# RF.net
KiCad netlist of a schematic drawn in Altium Designer
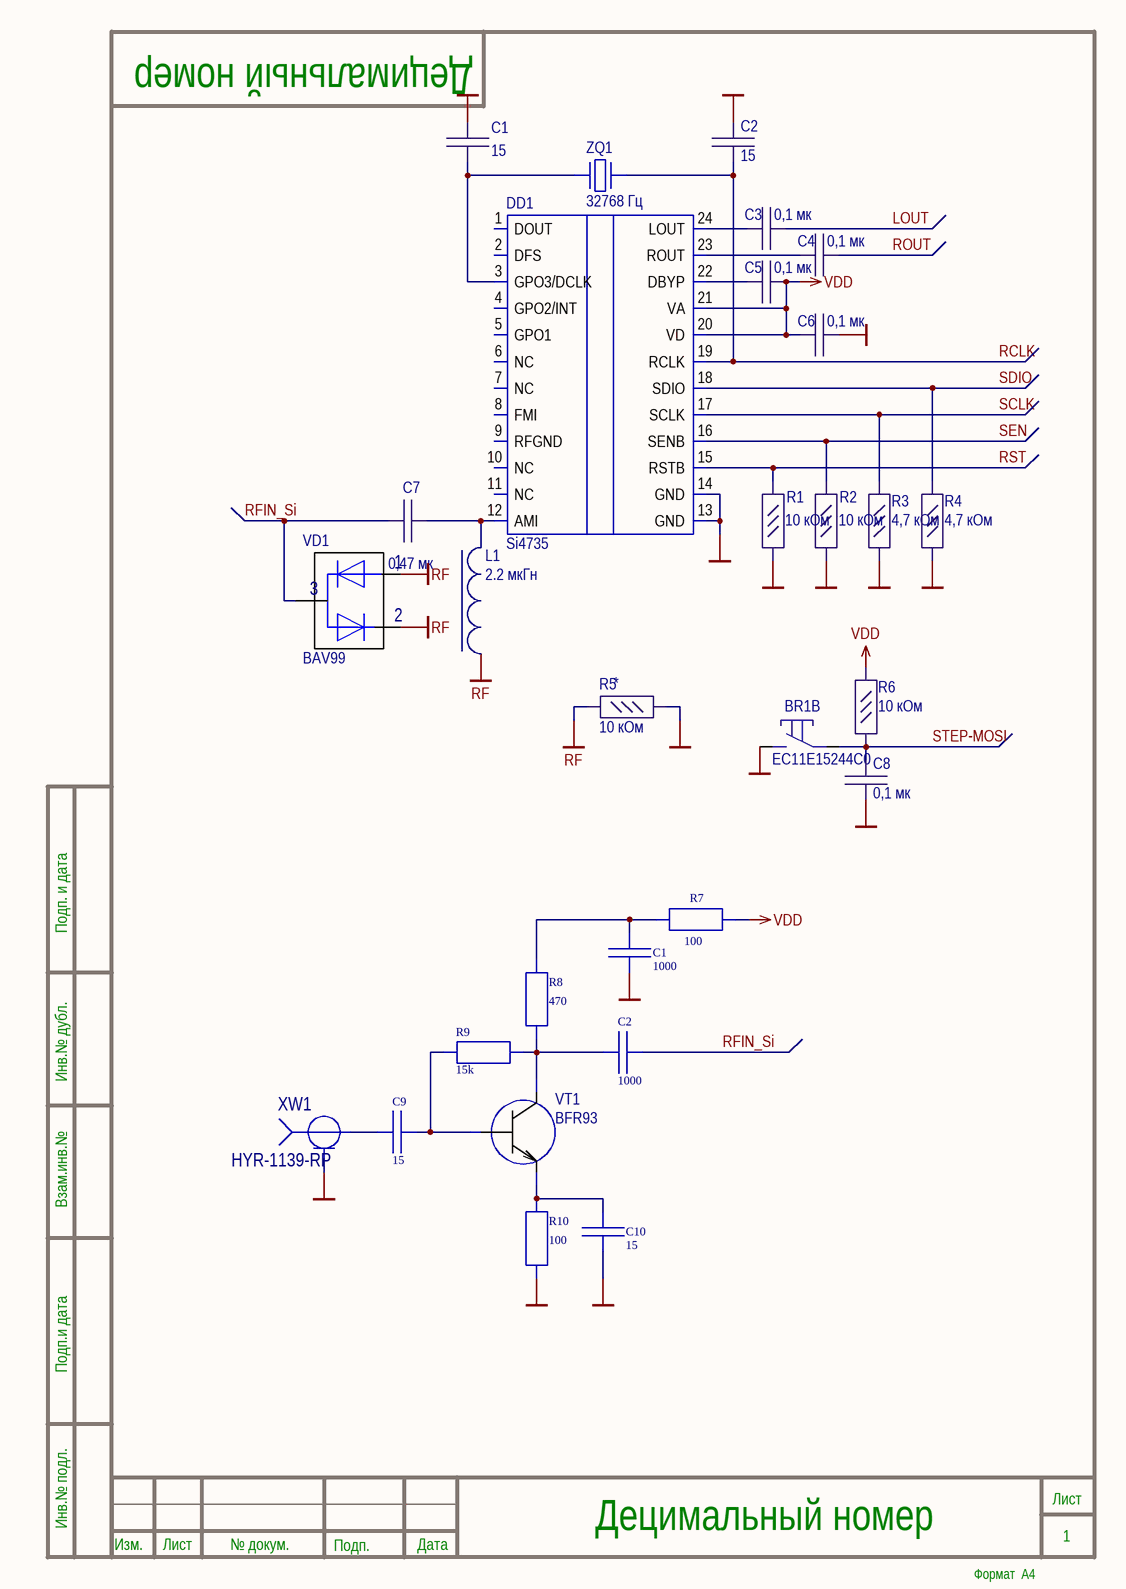
[diagram p0: RF.SchDoc]

(export (version "E")
  (design (tool "Eeschema 10.0.6"))
  (components
    (comp (ref "BR1")
      (value "EC11E15244C0")
      (footprint "EC11")
      (libsource (lib "9.Commutation") (part "EC11E15244C0"))
    )
    (comp (ref "C1")
      (value "15")
      (footprint "C_0603")
      (description "CAP CER 15PF 50V C0G/NP0 0603")
      (fields
        (field (name "PART NUMBER") "GRM1885C1H150FA01D")
        (field (name "MANUFACTURER") "Murata Electronics")
      )
      (libsource (lib "Database_Lib") (part "Capasitor"))
    )
    (comp (ref "C2")
      (value "15")
      (footprint "C_0603")
      (description "CAP CER 15PF 50V C0G/NP0 0603")
      (fields
        (field (name "PART NUMBER") "GRM1885C1H150FA01D")
        (field (name "MANUFACTURER") "Murata Electronics")
      )
      (libsource (lib "Database_Lib") (part "Capasitor"))
    )
    (comp (ref "C3")
      (value "0,1 мк")
      (footprint "C_0603")
      (description "CAP CER 0.1UF 100V X7R 0603")
      (fields
        (field (name "PART NUMBER") "GRM188R72A104MA35D")
        (field (name "MANUFACTURER") "Murata Electronics")
      )
      (libsource (lib "Database_Lib") (part "Capasitor"))
    )
    (comp (ref "C4")
      (value "0,1 мк")
      (footprint "C_0603")
      (description "CAP CER 0.1UF 100V X7R 0603")
      (fields
        (field (name "PART NUMBER") "GRM188R72A104MA35D")
        (field (name "MANUFACTURER") "Murata Electronics")
      )
      (libsource (lib "Database_Lib") (part "Capasitor"))
    )
    (comp (ref "C5")
      (value "0,1 мк")
      (footprint "C_0603")
      (description "CAP CER 0.1UF 100V X7R 0603")
      (fields
        (field (name "PART NUMBER") "GRM188R72A104MA35D")
        (field (name "MANUFACTURER") "Murata Electronics")
      )
      (libsource (lib "Database_Lib") (part "Capasitor"))
    )
    (comp (ref "C6")
      (value "0,1 мк")
      (footprint "C_0603")
      (description "CAP CER 0.1UF 100V X7R 0603")
      (fields
        (field (name "PART NUMBER") "GRM188R72A104MA35D")
        (field (name "MANUFACTURER") "Murata Electronics")
      )
      (libsource (lib "Database_Lib") (part "Capasitor"))
    )
    (comp (ref "C7")
      (value "0,47 мк")
      (footprint "C_0603")
      (description "CAP CER 0.47UF 25V X7R 0603")
      (fields
        (field (name "PART NUMBER") "GRM188R71E474KA12D")
        (field (name "MANUFACTURER") "Murata Electronics")
      )
      (libsource (lib "Database_Lib") (part "Capasitor"))
    )
    (comp (ref "C8")
      (value "0,1 мк")
      (footprint "C_0603")
      (description "CAP CER 0.1UF 100V X7R 0603")
      (fields
        (field (name "PART NUMBER") "GRM188R72A104MA35D")
        (field (name "MANUFACTURER") "Murata Electronics")
      )
      (libsource (lib "Database_Lib") (part "Capasitor"))
    )
    (comp (ref "C9")
      (value "15")
      (footprint "C_0603")
      (description "Cap. 15 pF, 0603")
      (libsource (lib "Schlib1") (part "06035C100KAT2A"))
    )
    (comp (ref "C10")
      (value "15")
      (footprint "C_0603")
      (description "Cap. 15 pF, 0603")
      (libsource (lib "Schlib1") (part "06035C100KAT2A"))
    )
    (comp (ref "DD1")
      (value "Si4735")
      (footprint "SSOP-24")
      (description "BROADCAST AM/FM/SW/LW RADIO RECEIVER")
      (libsource (lib "2. Chips") (part "Si4735"))
    )
    (comp (ref "L1")
      (value "2.2 мкГн")
      (footprint "LQW18A")
      (description "0.22 мкГн, 0603, 2%")
      (libsource (lib "11. Inductors") (part "LQW18ANR22G"))
    )
    (comp (ref "R1")
      (value "10 кОм")
      (footprint "R_0603")
      (description "RES SMD 10K OHM 1% 1/10W 0603")
      (fields (field (name "PART NUMBER") "CR0603-FX-1002ELF") (field (name "MANUFACTURER") "Bourns Inc."))
      (libsource (lib "Database_Lib") (part "Resistor"))
    )
    (comp (ref "R2")
      (value "10 кОм")
      (footprint "R_0603")
      (description "RES SMD 10K OHM 1% 1/10W 0603")
      (fields (field (name "PART NUMBER") "CR0603-FX-1002ELF") (field (name "MANUFACTURER") "Bourns Inc."))
      (libsource (lib "Database_Lib") (part "Resistor"))
    )
    (comp (ref "R3")
      (value "4,7 кОм")
      (footprint "R_0603")
      (description "RES SMD 4.7K OHM 1% 1/10W 0603")
      (fields (field (name "PART NUMBER") "CR0603-FX-4701ELF") (field (name "MANUFACTURER") "Bourns Inc."))
      (libsource (lib "Database_Lib") (part "Resistor"))
    )
    (comp (ref "R4")
      (value "4,7 кОм")
      (footprint "R_0603")
      (description "RES SMD 4.7K OHM 1% 1/10W 0603")
      (fields (field (name "PART NUMBER") "CR0603-FX-4701ELF") (field (name "MANUFACTURER") "Bourns Inc."))
      (libsource (lib "Database_Lib") (part "Resistor"))
    )
    (comp (ref "R5")
      (value "10 кОм")
      (footprint "R_0603")
      (description "RES SMD 10K OHM 1% 1/10W 0603")
      (fields (field (name "PART NUMBER") "CR0603-FX-1002ELF") (field (name "MANUFACTURER") "Bourns Inc."))
      (libsource (lib "Database_Lib") (part "Resistor"))
    )
    (comp (ref "R6")
      (value "10 кОм")
      (footprint "R_0603")
      (description "RES SMD 10K OHM 1% 1/10W 0603")
      (fields (field (name "PART NUMBER") "CR0603-FX-1002ELF") (field (name "MANUFACTURER") "Bourns Inc."))
      (libsource (lib "Database_Lib") (part "Resistor"))
    )
    (comp (ref "R7")
      (value "100")
      (footprint "R_0603")
      (description "Res. 100 Ohm, 0603")
      (libsource (lib "Schlib1") (part "CR0603-FX-1000ELF"))
    )
    (comp (ref "R8")
      (value "470")
      (footprint "R_0603")
      (description "Res. 470 Ohm, 0603")
      (libsource (lib "Schlib1") (part "RC0603JR-07470RL"))
    )
    (comp (ref "R9")
      (value "15k")
      (footprint "R_0603")
      (description "Res. 15 kOhm, 0603")
      (libsource (lib "Schlib1") (part "RC0603FR-0715KL"))
    )
    (comp (ref "R10")
      (value "100")
      (footprint "R_0603")
      (description "Res. 100 Ohm, 0603")
      (libsource (lib "Schlib1") (part "CR0603-FX-1000ELF"))
    )
    (comp (ref "VD1") (value "BAV99") (footprint "SOT23") (libsource (lib "3. Diodes") (part "BAV99")))
    (comp (ref "VT1")
      (value "BFR93")
      (footprint "BFR93 SOT95P230X110-3L")
      (libsource (lib "Schlib1") (part "BFR93"))
    )
    (comp (ref "XW1")
      (value "HYR-1139-RP")
      (footprint "SMA (HYR1139)")
      (libsource (lib "Schlib1") (part "HYR-1139-RP"))
    )
    (comp (ref "ZQ1")
      (value "32768 Гц")
      (footprint "DT-38T")
      (libsource (lib "5. Resonarors") (part "FTX32.768K12.5D8-20D"))
    )
    (comp (ref "С1")
      (value "1000")
      (footprint "C_0603")
      (description "Cap. 1000nF, 0603")
      (libsource (lib "Schlib1") (part "06035A102JAT2A"))
    )
    (comp (ref "С2")
      (value "1000")
      (footprint "C_0603")
      (description "Cap. 1000nF, 0603")
      (libsource (lib "Schlib1") (part "06035A102JAT2A"))
    )
  )
  (nets
    (net (code "1") (name "/LOUT") (class "Default")
      (node (ref "C3") (pin "1") (pinfunction "1_1") (pintype "passive"))
    )
    (net (code "2") (name "/RCLK") (class "Default")
      (node (ref "C2") (pin "1") (pinfunction "1_1") (pintype "passive"))
      (node (ref "DD1") (pin "19") (pinfunction "RCLK_19") (pintype "passive"))
      (node (ref "ZQ1") (pin "1") (pinfunction "1_1") (pintype "passive"))
    )
    (net (code "3") (name "/RFIN_Si") (class "Default")
      (node (ref "C7") (pin "1") (pinfunction "1_1") (pintype "passive"))
      (node (ref "VD1") (pin "3") (pinfunction "C1A2_3") (pintype "passive"))
      (node (ref "С2") (pin "1") (pinfunction "1_1") (pintype "passive"))
    )
    (net (code "4") (name "/ROUT") (class "Default")
      (node (ref "C4") (pin "1") (pinfunction "1_1") (pintype "passive"))
    )
    (net (code "5") (name "/RST") (class "Default")
      (node (ref "DD1") (pin "15") (pinfunction "RSTB_15") (pintype "passive"))
      (node (ref "R1") (pin "2") (pinfunction "2_2") (pintype "passive"))
    )
    (net (code "6") (name "/SCLK") (class "Default")
      (node (ref "DD1") (pin "17") (pinfunction "SCLK_17") (pintype "passive"))
      (node (ref "R3") (pin "2") (pinfunction "2_2") (pintype "passive"))
    )
    (net (code "7") (name "/SDIO") (class "Default")
      (node (ref "DD1") (pin "18") (pinfunction "SDIO_18") (pintype "passive"))
      (node (ref "R4") (pin "2") (pinfunction "2_2") (pintype "passive"))
    )
    (net (code "8") (name "/SEN") (class "Default")
      (node (ref "DD1") (pin "16") (pinfunction "SENB_16") (pintype "passive"))
      (node (ref "R2") (pin "2") (pinfunction "2_2") (pintype "passive"))
    )
    (net (code "9") (name "/STEP-MOSI") (class "Default")
      (node (ref "BR1") (pin "E") (pinfunction "E_E") (pintype "passive"))
      (node (ref "C8") (pin "1") (pinfunction "1_1") (pintype "passive"))
      (node (ref "R6") (pin "2") (pinfunction "2_2") (pintype "passive"))
    )
    (net (code "10") (name "GND") (class "Default")
      (node (ref "BR1") (pin "D") (pinfunction "D_D") (pintype "passive"))
      (node (ref "C1") (pin "2") (pinfunction "2_2") (pintype "passive"))
      (node (ref "C10") (pin "1") (pinfunction "1_1") (pintype "passive"))
      (node (ref "C2") (pin "2") (pinfunction "2_2") (pintype "passive"))
      (node (ref "C6") (pin "1") (pinfunction "1_1") (pintype "passive"))
      (node (ref "C8") (pin "2") (pinfunction "2_2") (pintype "passive"))
      (node (ref "DD1") (pin "13") (pinfunction "GND_13") (pintype "passive"))
      (node (ref "DD1") (pin "14") (pinfunction "GND_14") (pintype "passive"))
      (node (ref "R1") (pin "1") (pinfunction "1_1") (pintype "passive"))
      (node (ref "R10") (pin "1") (pinfunction "1_1") (pintype "passive"))
      (node (ref "R2") (pin "1") (pinfunction "1_1") (pintype "passive"))
      (node (ref "R3") (pin "1") (pinfunction "1_1") (pintype "passive"))
      (node (ref "R4") (pin "1") (pinfunction "1_1") (pintype "passive"))
      (node (ref "R5") (pin "1") (pinfunction "1_1") (pintype "passive"))
      (node (ref "XW1") (pin "1") (pinfunction "1_1") (pintype "passive"))
      (node (ref "С1") (pin "1") (pinfunction "1_1") (pintype "passive"))
    )
    (net (code "11") (name "Net-(C9-Pad1)") (class "Default")
      (node (ref "C9") (pin "1") (pinfunction "1_1") (pintype "passive"))
      (node (ref "XW1") (pin "2") (pinfunction "2_2") (pintype "passive"))
    )
    (net (code "12") (name "Net-(DD1-AMI)") (class "Default")
      (node (ref "C7") (pin "2") (pinfunction "2_2") (pintype "passive"))
      (node (ref "DD1") (pin "12") (pinfunction "AMI_12") (pintype "passive"))
      (node (ref "L1") (pin "2") (pinfunction "2_2") (pintype "passive"))
    )
    (net (code "13") (name "Net-(DD1-DBYP)") (class "Default")
      (node (ref "C5") (pin "2") (pinfunction "2_2") (pintype "passive"))
      (node (ref "DD1") (pin "22") (pinfunction "DBYP_22") (pintype "passive"))
    )
    (net (code "14") (name "Net-(DD1-GPO3{slash}DCLK)") (class "Default")
      (node (ref "C1") (pin "1") (pinfunction "1_1") (pintype "passive"))
      (node (ref "DD1") (pin "3") (pinfunction "GPO3/DCLK_3") (pintype "passive"))
      (node (ref "ZQ1") (pin "2") (pinfunction "2_2") (pintype "passive"))
    )
    (net (code "15") (name "Net-(DD1-LOUT)") (class "Default")
      (node (ref "C3") (pin "2") (pinfunction "2_2") (pintype "passive"))
      (node (ref "DD1") (pin "24") (pinfunction "LOUT_24") (pintype "passive"))
    )
    (net (code "16") (name "Net-(DD1-ROUT)") (class "Default")
      (node (ref "C4") (pin "2") (pinfunction "2_2") (pintype "passive"))
      (node (ref "DD1") (pin "23") (pinfunction "ROUT_23") (pintype "passive"))
    )
    (net (code "17") (name "Net-(R7-Pad1)") (class "Default")
      (node (ref "R7") (pin "1") (pinfunction "1_1") (pintype "passive"))
      (node (ref "R8") (pin "2") (pinfunction "2_2") (pintype "passive"))
      (node (ref "С1") (pin "2") (pinfunction "2_2") (pintype "passive"))
    )
    (net (code "18") (name "Net-(VT1-B)") (class "Default")
      (node (ref "C9") (pin "2") (pinfunction "2_2") (pintype "passive"))
      (node (ref "R9") (pin "1") (pinfunction "1_1") (pintype "passive"))
      (node (ref "VT1") (pin "1") (pinfunction "B_1") (pintype "passive"))
    )
    (net (code "19") (name "Net-(VT1-C)") (class "Default")
      (node (ref "R8") (pin "1") (pinfunction "1_1") (pintype "passive"))
      (node (ref "R9") (pin "2") (pinfunction "2_2") (pintype "passive"))
      (node (ref "VT1") (pin "3") (pinfunction "C_3") (pintype "passive"))
      (node (ref "С2") (pin "2") (pinfunction "2_2") (pintype "passive"))
    )
    (net (code "20") (name "Net-(VT1-E)") (class "Default")
      (node (ref "C10") (pin "2") (pinfunction "2_2") (pintype "passive"))
      (node (ref "R10") (pin "2") (pinfunction "2_2") (pintype "passive"))
      (node (ref "VT1") (pin "2") (pinfunction "E_2") (pintype "passive"))
    )
    (net (code "21") (name "RF") (class "Default")
      (node (ref "L1") (pin "1") (pinfunction "1_1") (pintype "passive"))
      (node (ref "R5") (pin "2") (pinfunction "2_2") (pintype "passive"))
      (node (ref "VD1") (pin "1") (pinfunction "A1_1") (pintype "passive"))
      (node (ref "VD1") (pin "2") (pinfunction "C2_2") (pintype "passive"))
    )
    (net (code "22") (name "VDD") (class "Default")
      (node (ref "C5") (pin "1") (pinfunction "1_1") (pintype "passive"))
      (node (ref "C6") (pin "2") (pinfunction "2_2") (pintype "passive"))
      (node (ref "DD1") (pin "20") (pinfunction "VD_20") (pintype "passive"))
      (node (ref "DD1") (pin "21") (pinfunction "VA_21") (pintype "passive"))
      (node (ref "R6") (pin "1") (pinfunction "1_1") (pintype "passive"))
      (node (ref "R7") (pin "2") (pinfunction "2_2") (pintype "passive"))
    )
    (net (code "23") (name "unconnected-(DD1-DFS-Pad2)") (class "Default")
      (node (ref "DD1") (pin "2") (pinfunction "DFS_2") (pintype "passive"))
    )
    (net (code "24") (name "unconnected-(DD1-DOUT-Pad1)") (class "Default")
      (node (ref "DD1") (pin "1") (pinfunction "DOUT_1") (pintype "passive"))
    )
    (net (code "25") (name "unconnected-(DD1-FMI-Pad8)") (class "Default")
      (node (ref "DD1") (pin "8") (pinfunction "FMI_8") (pintype "passive"))
    )
    (net (code "26") (name "unconnected-(DD1-GPO1-Pad5)") (class "Default")
      (node (ref "DD1") (pin "5") (pinfunction "GPO1_5") (pintype "passive"))
    )
    (net (code "27") (name "unconnected-(DD1-GPO2{slash}INT-Pad4)") (class "Default")
      (node (ref "DD1") (pin "4") (pinfunction "GPO2/INT_4") (pintype "passive"))
    )
    (net (code "28") (name "unconnected-(DD1-NC-Pad6)") (class "Default")
      (node (ref "DD1") (pin "6") (pinfunction "NC_6") (pintype "passive"))
    )
    (net (code "29") (name "unconnected-(DD1-NC-Pad7)") (class "Default")
      (node (ref "DD1") (pin "7") (pinfunction "NC_7") (pintype "passive"))
    )
    (net (code "30") (name "unconnected-(DD1-NC-Pad10)") (class "Default")
      (node (ref "DD1") (pin "10") (pinfunction "NC_10") (pintype "passive"))
    )
    (net (code "31") (name "unconnected-(DD1-NC-Pad11)") (class "Default")
      (node (ref "DD1") (pin "11") (pinfunction "NC_11") (pintype "passive"))
    )
    (net (code "32") (name "unconnected-(DD1-RFGND-Pad9)") (class "Default")
      (node (ref "DD1") (pin "9") (pinfunction "RFGND_9") (pintype "passive"))
    )
  )
)
